# MinieasySens-RS485_V12-Build015.net
KiCad netlist of a schematic drawn in EAGLE
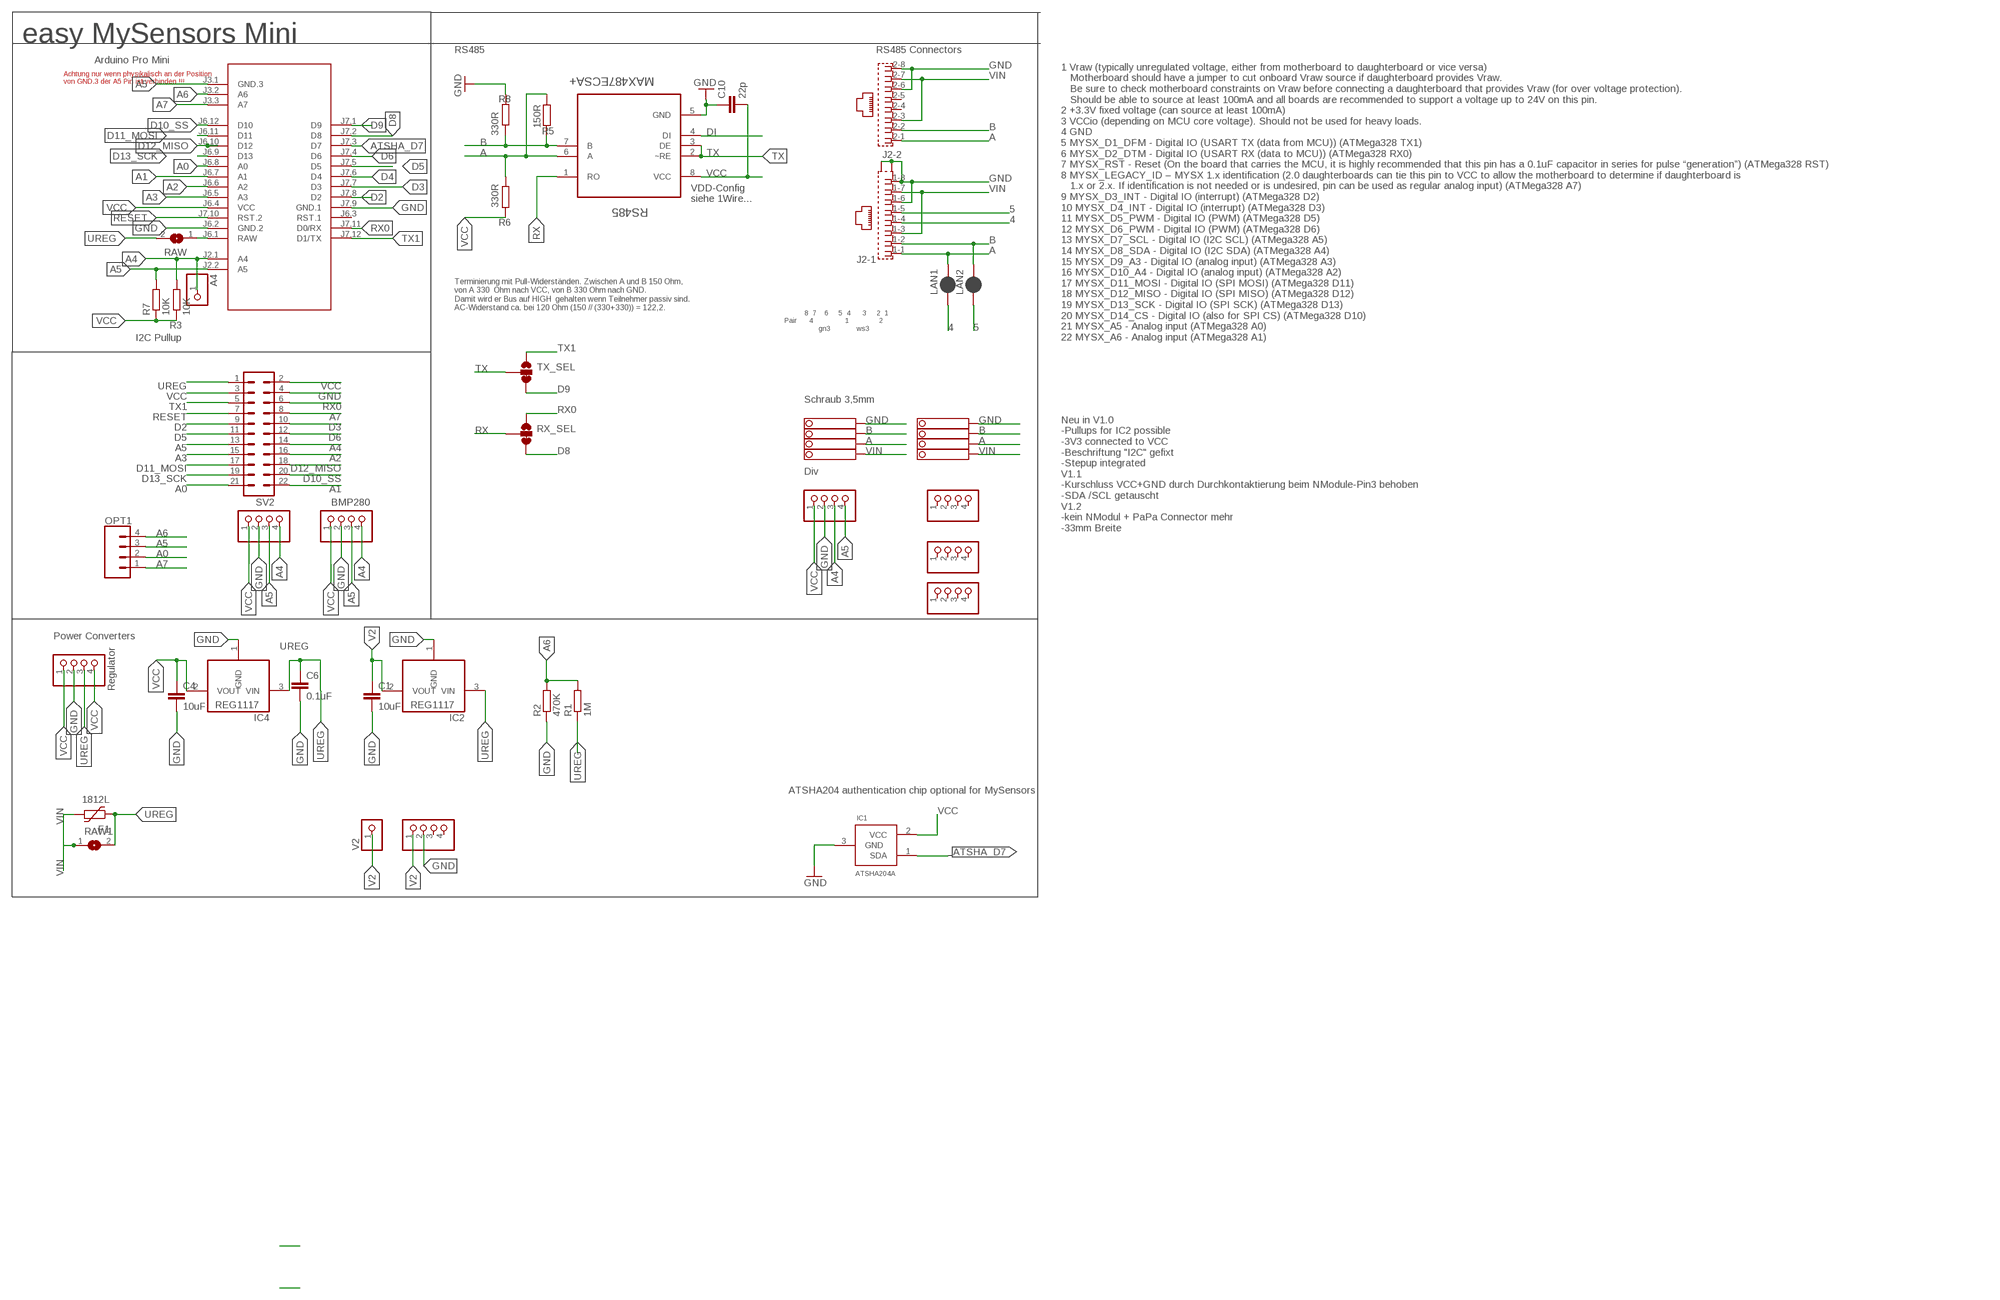
[diagram p0: schematic, sheet 1]

(export (version "E")
  (design (tool "Eeschema 10.0.6"))
  (components
    (comp (ref "A4")
      (value "PINHD-1X1")
      (footprint "eagle-import:1X01")
      (libsource (lib "eagle-import") (part "PINHD-1X1"))
    )
    (comp (ref "BH1750")
      (value "PINHD-1X04_2.54-S")
      (footprint "eagle-import:1X04-S")
      (libsource (lib "eagle-import") (part "PINHD-1X04_2.54-S"))
    )
    (comp (ref "C1")
      (value "10uF")
      (footprint "eagle-import:C1210")
      (libsource (lib "eagle-import") (part "C-EUC1210"))
    )
    (comp (ref "C4")
      (value "10uF")
      (footprint "eagle-import:C1210")
      (libsource (lib "eagle-import") (part "C-EUC1210"))
    )
    (comp (ref "C6")
      (value "0.1uF")
      (footprint "eagle-import:C1206")
      (libsource (lib "eagle-import") (part "C-EUC1206"))
    )
    (comp (ref "C10")
      (value "22p")
      (footprint "eagle-import:C0805")
      (libsource (lib "eagle-import") (part "C-EUC0805"))
    )
    (comp (ref "F1")
      (value "1812L")
      (footprint "eagle-import:1812L")
      (libsource (lib "eagle-import") (part "1812L"))
    )
    (comp (ref "I2C-1")
      (value "PINHD-1X04_2.54-S")
      (footprint "eagle-import:1X04-S")
      (libsource (lib "eagle-import") (part "PINHD-1X04_2.54-S"))
    )
    (comp (ref "I2C-2")
      (value "PINHD-1X04_2.54-S")
      (footprint "eagle-import:1X04-S")
      (libsource (lib "eagle-import") (part "PINHD-1X04_2.54-S"))
    )
    (comp (ref "IC1")
      (value "ATSHA204A")
      (footprint "eagle-import:SOT23")
      (libsource (lib "eagle-import") (part "ATSHA204A"))
    )
    (comp (ref "IC2")
      (value "REG1117")
      (footprint "eagle-import:SOT223")
      (libsource (lib "eagle-import") (part "REG1117"))
    )
    (comp (ref "IC4")
      (value "REG1117")
      (footprint "eagle-import:SOT223")
      (libsource (lib "eagle-import") (part "REG1117"))
    )
    (comp (ref "J2")
      (value "RJ45_2X_NARROW_SHILDPINS_NOCASE")
      (footprint "eagle-import:RJ45_2X_NARROW_SHILDPINS_NOCASE")
      (libsource (lib "eagle-import") (part "RJ45_2X_NARROW_SHILDPINS_NOCASE"))
    )
    (comp (ref "JP1")
      (value "PINHD-1X04_2.54-S")
      (footprint "eagle-import:1X04-S")
      (libsource (lib "eagle-import") (part "PINHD-1X04_2.54-S"))
    )
    (comp (ref "JP2")
      (value "PINHD-1X04_2.54-S")
      (footprint "eagle-import:1X04-S")
      (libsource (lib "eagle-import") (part "PINHD-1X04_2.54-S"))
    )
    (comp (ref "JP4")
      (value "PINHD-1X04_2.54-S")
      (footprint "eagle-import:1X04-S")
      (libsource (lib "eagle-import") (part "PINHD-1X04_2.54-S"))
    )
    (comp (ref "LAN1")
      (value "JUMPER-SMT_2_NC_PASTE_SILK")
      (footprint "eagle-import:SMT-JUMPER_2_NC_PASTE_SILK")
      (libsource (lib "eagle-import") (part "JUMPER-SMT_2_NC_PASTE_SILK"))
    )
    (comp (ref "LAN2")
      (value "JUMPER-SMT_2_NC_PASTE_SILK")
      (footprint "eagle-import:SMT-JUMPER_2_NC_PASTE_SILK")
      (libsource (lib "eagle-import") (part "JUMPER-SMT_2_NC_PASTE_SILK"))
    )
    (comp (ref "M1")
      (value "ARDUINO-PRO-MINI-3.3V#NP")
      (footprint "eagle-import:ARDUINO-PRO-MINI#NP")
      (libsource (lib "eagle-import") (part "ARDUINO-PRO-MINI-#NP3.3V"))
    )
    (comp (ref "OPT1")
      (value "CONN_04")
      (footprint "eagle-import:1X04")
      (libsource (lib "eagle-import") (part "CONN_04"))
    )
    (comp (ref "R1")
      (value "1M")
      (footprint "eagle-import:R0805")
      (libsource (lib "eagle-import") (part "R-EU_R0805"))
    )
    (comp (ref "R2")
      (value "470K")
      (footprint "eagle-import:R0805")
      (libsource (lib "eagle-import") (part "R-EU_R0805"))
    )
    (comp (ref "R3")
      (value "10K")
      (footprint "eagle-import:R0805")
      (libsource (lib "eagle-import") (part "R-EU_R0805"))
    )
    (comp (ref "R5")
      (value "150R")
      (footprint "eagle-import:R0805")
      (libsource (lib "eagle-import") (part "R-EU_R0805"))
    )
    (comp (ref "R6")
      (value "330R")
      (footprint "eagle-import:R0805")
      (libsource (lib "eagle-import") (part "R-EU_R0805"))
    )
    (comp (ref "R7")
      (value "10K")
      (footprint "eagle-import:R0805")
      (libsource (lib "eagle-import") (part "R-EU_R0805"))
    )
    (comp (ref "R8")
      (value "330R")
      (footprint "eagle-import:R0805")
      (libsource (lib "eagle-import") (part "R-EU_R0805"))
    )
    (comp (ref "RAW") (value "SJ") (footprint "eagle-import:SJ") (libsource (lib "eagle-import") (part "SJ")))
    (comp (ref "RAW1")
      (value "SJ")
      (footprint "eagle-import:SJ")
      (libsource (lib "eagle-import") (part "SJ"))
    )
    (comp (ref "RS485")
      (value "MAX487ECSA+")
      (footprint "eagle-import:SOIC127P600X175-8N")
      (libsource (lib "eagle-import") (part "MAX487ECSA+"))
    )
    (comp (ref "RX_SEL")
      (value "JUMPER-SMT_3_1-NC_TRACE_SILK")
      (footprint "eagle-import:SMT-JUMPER_3_1-NC_TRACE_SILK")
      (libsource (lib "eagle-import") (part "JUMPER-SMT_3_1-NC_TRACE_SILK"))
    )
    (comp (ref "STEPDWN")
      (value "PINHD-1X04_2.54-S")
      (footprint "eagle-import:1X04-S")
      (libsource (lib "eagle-import") (part "PINHD-1X04_2.54-S"))
    )
    (comp (ref "SV2")
      (value "MA11-2")
      (footprint "eagle-import:MA11-2")
      (libsource (lib "eagle-import") (part "MA11-2"))
    )
    (comp (ref "TX_SEL")
      (value "JUMPER-SMT_3_1-NC_TRACE_SILK")
      (footprint "eagle-import:SMT-JUMPER_3_1-NC_TRACE_SILK")
      (libsource (lib "eagle-import") (part "JUMPER-SMT_3_1-NC_TRACE_SILK"))
    )
    (comp (ref "V2")
      (value "PINHD-1X1")
      (footprint "eagle-import:1X01")
      (libsource (lib "eagle-import") (part "PINHD-1X1"))
    )
    (comp (ref "V2-")
      (value "PINHD-1X04_2.54-S")
      (footprint "eagle-import:1X04-S")
      (libsource (lib "eagle-import") (part "PINHD-1X04_2.54-S"))
    )
    (comp (ref "X1")
      (value "1751264")
      (footprint "eagle-import:1751264")
      (libsource (lib "eagle-import") (part "1751264"))
    )
    (comp (ref "X4")
      (value "1751264")
      (footprint "eagle-import:1751264")
      (libsource (lib "eagle-import") (part "1751264"))
    )
  )
  (nets
    (net (code "1") (name "/4") (class "Default")
      (node (ref "J2") (pin "1-4") (pinfunction "4_1-4") (pintype "passive"))
      (node (ref "LAN1") (pin "1") (pinfunction "1_1") (pintype "passive"))
    )
    (net (code "2") (name "/5") (class "Default")
      (node (ref "J2") (pin "1-5") (pinfunction "5_1-5") (pintype "passive"))
      (node (ref "LAN2") (pin "1") (pinfunction "1_1") (pintype "passive"))
    )
    (net (code "3") (name "/A") (class "Default")
      (node (ref "J2") (pin "1-1") (pinfunction "1_1-1") (pintype "passive"))
      (node (ref "J2") (pin "2-1") (pinfunction "1_2-1") (pintype "passive"))
      (node (ref "LAN1") (pin "2") (pinfunction "2_2") (pintype "passive"))
      (node (ref "R5") (pin "1") (pinfunction "1_1") (pintype "passive"))
      (node (ref "R6") (pin "2") (pinfunction "2_2") (pintype "passive"))
      (node (ref "RS485") (pin "6") (pinfunction "A_6") (pintype "bidirectional"))
      (node (ref "X1") (pin "2") (pinfunction "K_2") (pintype "passive"))
      (node (ref "X4") (pin "2") (pinfunction "K_2") (pintype "passive"))
    )
    (net (code "4") (name "/B") (class "Default")
      (node (ref "J2") (pin "1-2") (pinfunction "2_1-2") (pintype "passive"))
      (node (ref "J2") (pin "2-2") (pinfunction "2_2-2") (pintype "passive"))
      (node (ref "LAN2") (pin "2") (pinfunction "2_2") (pintype "passive"))
      (node (ref "R5") (pin "2") (pinfunction "2_2") (pintype "passive"))
      (node (ref "R8") (pin "1") (pinfunction "1_1") (pintype "passive"))
      (node (ref "RS485") (pin "7") (pinfunction "B_7") (pintype "bidirectional"))
      (node (ref "X1") (pin "3") (pinfunction "K_3") (pintype "passive"))
      (node (ref "X4") (pin "3") (pinfunction "K_3") (pintype "passive"))
    )
    (net (code "5") (name "/DI") (class "Default")
      (node (ref "RS485") (pin "4") (pinfunction "DI_4") (pintype "input"))
    )
    (net (code "6") (name "/VIN") (class "Default")
      (node (ref "F1") (pin "P$2") (pinfunction "2_P$2") (pintype "passive"))
      (node (ref "J2") (pin "1-3") (pinfunction "3_1-3") (pintype "passive"))
      (node (ref "J2") (pin "1-7") (pinfunction "7_1-7") (pintype "passive"))
      (node (ref "J2") (pin "2-3") (pinfunction "3_2-3") (pintype "passive"))
      (node (ref "J2") (pin "2-7") (pinfunction "7_2-7") (pintype "passive"))
      (node (ref "RAW1") (pin "1") (pinfunction "1_1") (pintype "passive"))
      (node (ref "X1") (pin "1") (pinfunction "K_1") (pintype "passive"))
      (node (ref "X4") (pin "1") (pinfunction "K_1") (pintype "passive"))
    )
    (net (code "7") (name "A0") (class "Default")
      (node (ref "M1") (pin "J6.8") (pinfunction "A0_J6.8") (pintype "bidirectional"))
      (node (ref "OPT1") (pin "2") (pinfunction "2_2") (pintype "passive"))
      (node (ref "SV2") (pin "21") (pinfunction "21_21") (pintype "passive"))
    )
    (net (code "8") (name "A1") (class "Default")
      (node (ref "M1") (pin "J6.7") (pinfunction "A1_J6.7") (pintype "bidirectional"))
      (node (ref "SV2") (pin "22") (pinfunction "22_22") (pintype "passive"))
    )
    (net (code "9") (name "A2") (class "Default")
      (node (ref "M1") (pin "J6.6") (pinfunction "A2_J6.6") (pintype "bidirectional"))
      (node (ref "SV2") (pin "16") (pinfunction "16_16") (pintype "passive"))
    )
    (net (code "10") (name "A3") (class "Default")
      (node (ref "M1") (pin "J6.5") (pinfunction "A3_J6.5") (pintype "bidirectional"))
      (node (ref "SV2") (pin "15") (pinfunction "15_15") (pintype "passive"))
    )
    (net (code "11") (name "A4") (class "Default")
      (node (ref "A4") (pin "1") (pinfunction "1_1") (pintype "passive"))
      (node (ref "BH1750") (pin "4") (pinfunction "4_4") (pintype "passive"))
      (node (ref "I2C-1") (pin "4") (pinfunction "4_4") (pintype "passive"))
      (node (ref "I2C-2") (pin "3") (pinfunction "3_3") (pintype "passive"))
      (node (ref "M1") (pin "J2.1") (pinfunction "A4_J2.1") (pintype "bidirectional"))
      (node (ref "R3") (pin "2") (pinfunction "2_2") (pintype "passive"))
      (node (ref "SV2") (pin "14") (pinfunction "14_14") (pintype "passive"))
    )
    (net (code "12") (name "A5") (class "Default")
      (node (ref "BH1750") (pin "3") (pinfunction "3_3") (pintype "passive"))
      (node (ref "I2C-1") (pin "3") (pinfunction "3_3") (pintype "passive"))
      (node (ref "I2C-2") (pin "4") (pinfunction "4_4") (pintype "passive"))
      (node (ref "M1") (pin "J2.2") (pinfunction "A5_J2.2") (pintype "bidirectional"))
      (node (ref "M1") (pin "J3.1") (pinfunction "GND.3_J3.1") (pintype "bidirectional"))
      (node (ref "OPT1") (pin "3") (pinfunction "3_3") (pintype "passive"))
      (node (ref "R7") (pin "2") (pinfunction "2_2") (pintype "passive"))
      (node (ref "SV2") (pin "13") (pinfunction "13_13") (pintype "passive"))
    )
    (net (code "13") (name "A6") (class "Default")
      (node (ref "M1") (pin "J3.2") (pinfunction "A6_J3.2") (pintype "bidirectional"))
      (node (ref "OPT1") (pin "4") (pinfunction "4_4") (pintype "passive"))
      (node (ref "R1") (pin "2") (pinfunction "2_2") (pintype "passive"))
      (node (ref "R2") (pin "2") (pinfunction "2_2") (pintype "passive"))
    )
    (net (code "14") (name "A7") (class "Default")
      (node (ref "M1") (pin "J3.3") (pinfunction "A7_J3.3") (pintype "bidirectional"))
      (node (ref "OPT1") (pin "1") (pinfunction "1_1") (pintype "passive"))
      (node (ref "SV2") (pin "8") (pinfunction "8_8") (pintype "passive"))
    )
    (net (code "15") (name "ATSHA_D7") (class "Default")
      (node (ref "IC1") (pin "1") (pinfunction "SDA_1") (pintype "bidirectional"))
      (node (ref "M1") (pin "J7.3") (pinfunction "D7_J7.3") (pintype "bidirectional"))
    )
    (net (code "16") (name "D2") (class "Default")
      (node (ref "M1") (pin "J7.8") (pinfunction "D2_J7.8") (pintype "bidirectional"))
      (node (ref "SV2") (pin "9") (pinfunction "9_9") (pintype "passive"))
    )
    (net (code "17") (name "D3") (class "Default")
      (node (ref "M1") (pin "J7.7") (pinfunction "D3_J7.7") (pintype "bidirectional"))
      (node (ref "SV2") (pin "10") (pinfunction "10_10") (pintype "passive"))
    )
    (net (code "18") (name "D4") (class "Default")
      (node (ref "M1") (pin "J7.6") (pinfunction "D4_J7.6") (pintype "bidirectional"))
    )
    (net (code "19") (name "D5") (class "Default")
      (node (ref "M1") (pin "J7.5") (pinfunction "D5_J7.5") (pintype "bidirectional"))
      (node (ref "SV2") (pin "11") (pinfunction "11_11") (pintype "passive"))
    )
    (net (code "20") (name "D6") (class "Default")
      (node (ref "M1") (pin "J7.4") (pinfunction "D6_J7.4") (pintype "bidirectional"))
      (node (ref "SV2") (pin "12") (pinfunction "12_12") (pintype "passive"))
    )
    (net (code "21") (name "D8") (class "Default")
      (node (ref "M1") (pin "J7.2") (pinfunction "D8_J7.2") (pintype "bidirectional"))
      (node (ref "RX_SEL") (pin "3") (pinfunction "3_3") (pintype "passive"))
    )
    (net (code "22") (name "D9") (class "Default")
      (node (ref "M1") (pin "J7.1") (pinfunction "D9_J7.1") (pintype "bidirectional"))
      (node (ref "TX_SEL") (pin "3") (pinfunction "3_3") (pintype "passive"))
    )
    (net (code "23") (name "D10_SS") (class "Default")
      (node (ref "M1") (pin "J6.12") (pinfunction "D10_J6.12") (pintype "bidirectional"))
      (node (ref "SV2") (pin "20") (pinfunction "20_20") (pintype "passive"))
    )
    (net (code "24") (name "D11_MOSI") (class "Default")
      (node (ref "M1") (pin "J6.11") (pinfunction "D11_J6.11") (pintype "bidirectional"))
      (node (ref "SV2") (pin "17") (pinfunction "17_17") (pintype "passive"))
    )
    (net (code "25") (name "D12_MISO") (class "Default")
      (node (ref "M1") (pin "J6.10") (pinfunction "D12_J6.10") (pintype "bidirectional"))
      (node (ref "SV2") (pin "18") (pinfunction "18_18") (pintype "passive"))
    )
    (net (code "26") (name "D13_SCK") (class "Default")
      (node (ref "M1") (pin "J6.9") (pinfunction "D13_J6.9") (pintype "bidirectional"))
      (node (ref "SV2") (pin "19") (pinfunction "19_19") (pintype "passive"))
    )
    (net (code "27") (name "GND") (class "Default")
      (node (ref "BH1750") (pin "2") (pinfunction "2_2") (pintype "passive"))
      (node (ref "C1") (pin "2") (pinfunction "2_2") (pintype "passive"))
      (node (ref "C10") (pin "1") (pinfunction "1_1") (pintype "passive"))
      (node (ref "C4") (pin "2") (pinfunction "2_2") (pintype "passive"))
      (node (ref "C6") (pin "2") (pinfunction "2_2") (pintype "passive"))
      (node (ref "I2C-1") (pin "2") (pinfunction "2_2") (pintype "passive"))
      (node (ref "I2C-2") (pin "2") (pinfunction "2_2") (pintype "passive"))
      (node (ref "IC1") (pin "3") (pinfunction "GND_3") (pintype "bidirectional"))
      (node (ref "IC2") (pin "1") (pinfunction "GND_1") (pintype "power_in"))
      (node (ref "IC4") (pin "1") (pinfunction "GND_1") (pintype "power_in"))
      (node (ref "J2") (pin "1-6") (pinfunction "6_1-6") (pintype "passive"))
      (node (ref "J2") (pin "1-8") (pinfunction "8_1-8") (pintype "passive"))
      (node (ref "J2") (pin "2-6") (pinfunction "6_2-6") (pintype "passive"))
      (node (ref "J2") (pin "2-8") (pinfunction "8_2-8") (pintype "passive"))
      (node (ref "J2") (pin "G1") (pinfunction "S1_G1") (pintype "passive"))
      (node (ref "J2") (pin "G3") (pinfunction "S2_G3") (pintype "passive"))
      (node (ref "M1") (pin "J6.2") (pinfunction "GND.2_J6.2") (pintype "power_in"))
      (node (ref "M1") (pin "J7.9") (pinfunction "GND.1_J7.9") (pintype "power_in"))
      (node (ref "R2") (pin "1") (pinfunction "1_1") (pintype "passive"))
      (node (ref "R8") (pin "2") (pinfunction "2_2") (pintype "passive"))
      (node (ref "RS485") (pin "5") (pinfunction "GND_5") (pintype "passive"))
      (node (ref "STEPDWN") (pin "2") (pinfunction "2_2") (pintype "passive"))
      (node (ref "SV2") (pin "4") (pinfunction "4_4") (pintype "passive"))
      (node (ref "V2-") (pin "2") (pinfunction "2_2") (pintype "passive"))
      (node (ref "X1") (pin "4") (pinfunction "K_4") (pintype "passive"))
      (node (ref "X4") (pin "4") (pinfunction "K_4") (pintype "passive"))
    )
    (net (code "28") (name "Net-(M1-RAW)") (class "Default")
      (node (ref "M1") (pin "J6.1") (pinfunction "RAW_J6.1") (pintype "power_in"))
      (node (ref "RAW") (pin "1") (pinfunction "1_1") (pintype "passive"))
    )
    (net (code "29") (name "RESET") (class "Default")
      (node (ref "M1") (pin "J7.10") (pinfunction "RST.2_J7.10") (pintype "bidirectional"))
      (node (ref "SV2") (pin "7") (pinfunction "7_7") (pintype "passive"))
    )
    (net (code "30") (name "RX") (class "Default")
      (node (ref "RS485") (pin "1") (pinfunction "RO_1") (pintype "output"))
      (node (ref "RX_SEL") (pin "2") (pinfunction "2_2") (pintype "passive"))
    )
    (net (code "31") (name "RX0") (class "Default")
      (node (ref "M1") (pin "J7.11") (pinfunction "D0/RX_J7.11") (pintype "bidirectional"))
      (node (ref "RX_SEL") (pin "1") (pinfunction "1_1") (pintype "passive"))
      (node (ref "SV2") (pin "6") (pinfunction "6_6") (pintype "passive"))
    )
    (net (code "32") (name "TX") (class "Default")
      (node (ref "RS485") (pin "2") (pinfunction "~{RE}_2") (pintype "input"))
      (node (ref "RS485") (pin "3") (pinfunction "DE_3") (pintype "input"))
      (node (ref "TX_SEL") (pin "2") (pinfunction "2_2") (pintype "passive"))
    )
    (net (code "33") (name "TX1") (class "Default")
      (node (ref "M1") (pin "J7.12") (pinfunction "D1/TX_J7.12") (pintype "bidirectional"))
      (node (ref "SV2") (pin "5") (pinfunction "5_5") (pintype "passive"))
      (node (ref "TX_SEL") (pin "1") (pinfunction "1_1") (pintype "passive"))
    )
    (net (code "34") (name "UREG") (class "Default")
      (node (ref "C6") (pin "1") (pinfunction "1_1") (pintype "passive"))
      (node (ref "F1") (pin "P$1") (pinfunction "1_P$1") (pintype "passive"))
      (node (ref "IC2") (pin "3") (pinfunction "VIN_3") (pintype "input"))
      (node (ref "IC4") (pin "3") (pinfunction "VIN_3") (pintype "input"))
      (node (ref "R1") (pin "1") (pinfunction "1_1") (pintype "passive"))
      (node (ref "RAW") (pin "2") (pinfunction "2_2") (pintype "passive"))
      (node (ref "RAW1") (pin "2") (pinfunction "2_2") (pintype "passive"))
      (node (ref "STEPDWN") (pin "3") (pinfunction "3_3") (pintype "passive"))
      (node (ref "SV2") (pin "1") (pinfunction "1_1") (pintype "passive"))
    )
    (net (code "35") (name "V2") (class "Default")
      (node (ref "C1") (pin "1") (pinfunction "1_1") (pintype "passive"))
      (node (ref "IC2") (pin "2") (pinfunction "VOUT_2") (pintype "output"))
      (node (ref "V2") (pin "1") (pinfunction "1_1") (pintype "passive"))
      (node (ref "V2-") (pin "1") (pinfunction "1_1") (pintype "passive"))
    )
    (net (code "36") (name "VCC") (class "Default")
      (node (ref "BH1750") (pin "1") (pinfunction "1_1") (pintype "passive"))
      (node (ref "C10") (pin "2") (pinfunction "2_2") (pintype "passive"))
      (node (ref "C4") (pin "1") (pinfunction "1_1") (pintype "passive"))
      (node (ref "I2C-1") (pin "1") (pinfunction "1_1") (pintype "passive"))
      (node (ref "I2C-2") (pin "1") (pinfunction "1_1") (pintype "passive"))
      (node (ref "IC1") (pin "2") (pinfunction "VCC_2") (pintype "bidirectional"))
      (node (ref "IC4") (pin "2") (pinfunction "VOUT_2") (pintype "output"))
      (node (ref "M1") (pin "J6.4") (pinfunction "VCC_J6.4") (pintype "power_in"))
      (node (ref "R3") (pin "1") (pinfunction "1_1") (pintype "passive"))
      (node (ref "R6") (pin "1") (pinfunction "1_1") (pintype "passive"))
      (node (ref "R7") (pin "1") (pinfunction "1_1") (pintype "passive"))
      (node (ref "RS485") (pin "8") (pinfunction "VCC_8") (pintype "power_in"))
      (node (ref "STEPDWN") (pin "1") (pinfunction "1_1") (pintype "passive"))
      (node (ref "STEPDWN") (pin "4") (pinfunction "4_4") (pintype "passive"))
      (node (ref "SV2") (pin "2") (pinfunction "2_2") (pintype "passive"))
      (node (ref "SV2") (pin "3") (pinfunction "3_3") (pintype "passive"))
    )
    (net (code "37") (name "unconnected-(J2B-4-Pad2-4)") (class "Default")
      (node (ref "J2") (pin "2-4") (pinfunction "4_2-4") (pintype "passive"))
    )
    (net (code "38") (name "unconnected-(J2B-5-Pad2-5)") (class "Default")
      (node (ref "J2") (pin "2-5") (pinfunction "5_2-5") (pintype "passive"))
    )
    (net (code "39") (name "unconnected-(JP1-Pad1)") (class "Default")
      (node (ref "JP1") (pin "1") (pinfunction "1_1") (pintype "passive"))
    )
    (net (code "40") (name "unconnected-(JP1-Pad2)") (class "Default")
      (node (ref "JP1") (pin "2") (pinfunction "2_2") (pintype "passive"))
    )
    (net (code "41") (name "unconnected-(JP1-Pad3)") (class "Default")
      (node (ref "JP1") (pin "3") (pinfunction "3_3") (pintype "passive"))
    )
    (net (code "42") (name "unconnected-(JP1-Pad4)") (class "Default")
      (node (ref "JP1") (pin "4") (pinfunction "4_4") (pintype "passive"))
    )
    (net (code "43") (name "unconnected-(JP2-Pad1)") (class "Default")
      (node (ref "JP2") (pin "1") (pinfunction "1_1") (pintype "passive"))
    )
    (net (code "44") (name "unconnected-(JP2-Pad2)") (class "Default")
      (node (ref "JP2") (pin "2") (pinfunction "2_2") (pintype "passive"))
    )
    (net (code "45") (name "unconnected-(JP2-Pad3)") (class "Default")
      (node (ref "JP2") (pin "3") (pinfunction "3_3") (pintype "passive"))
    )
    (net (code "46") (name "unconnected-(JP2-Pad4)") (class "Default")
      (node (ref "JP2") (pin "4") (pinfunction "4_4") (pintype "passive"))
    )
    (net (code "47") (name "unconnected-(JP4-Pad1)") (class "Default")
      (node (ref "JP4") (pin "1") (pinfunction "1_1") (pintype "passive"))
    )
    (net (code "48") (name "unconnected-(JP4-Pad2)") (class "Default")
      (node (ref "JP4") (pin "2") (pinfunction "2_2") (pintype "passive"))
    )
    (net (code "49") (name "unconnected-(JP4-Pad3)") (class "Default")
      (node (ref "JP4") (pin "3") (pinfunction "3_3") (pintype "passive"))
    )
    (net (code "50") (name "unconnected-(JP4-Pad4)") (class "Default")
      (node (ref "JP4") (pin "4") (pinfunction "4_4") (pintype "passive"))
    )
    (net (code "51") (name "unconnected-(M1-RST.1-PadJ6.3)") (class "Default")
      (node (ref "M1") (pin "J6.3") (pinfunction "RST.1_J6.3") (pintype "bidirectional"))
    )
    (net (code "52") (name "unconnected-(V2--Pad3)") (class "Default")
      (node (ref "V2-") (pin "3") (pinfunction "3_3") (pintype "passive"))
    )
    (net (code "53") (name "unconnected-(V2--Pad4)") (class "Default")
      (node (ref "V2-") (pin "4") (pinfunction "4_4") (pintype "passive"))
    )
  )
)
